# OECU_BASE2.net
KiCad netlist of a schematic drawn in Altium Designer
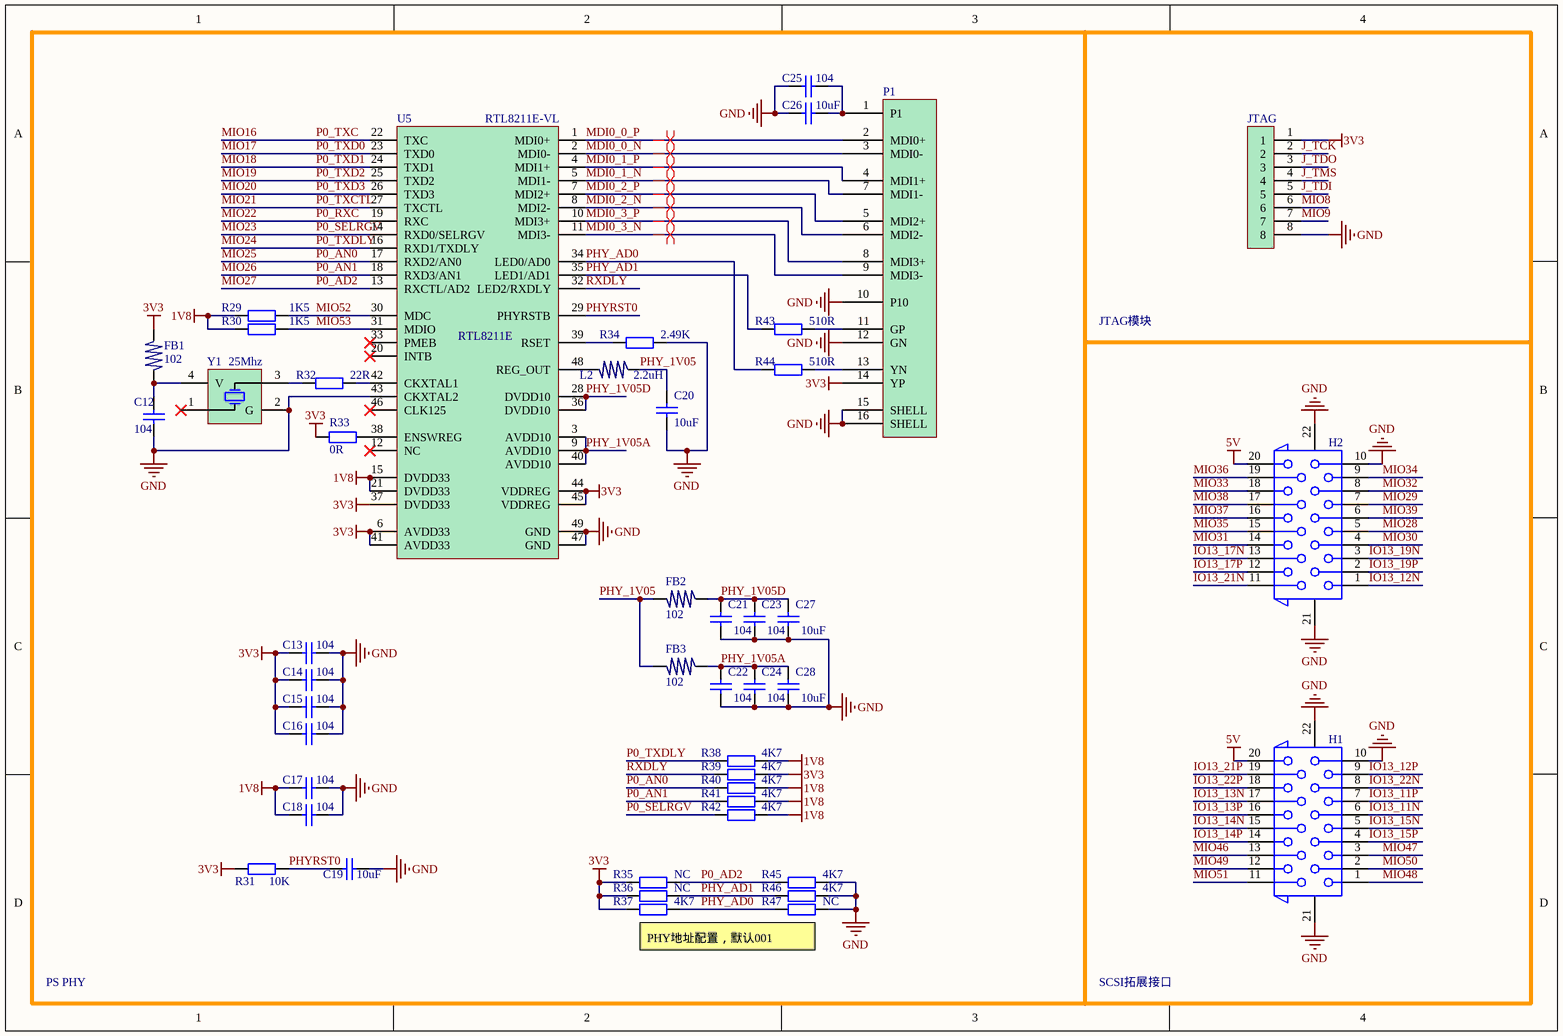
[diagram p0: OECU_BASE2.SchDoc]

(export (version "E")
  (design (tool "Eeschema 10.0.6"))
  (components
    (comp (ref "C12")
      (value "104")
      (footprint "0402")
      (description "贴片电容 0402")
      (libsource (lib "MT_Device") (part "CAP_0402"))
    )
    (comp (ref "C13")
      (value "104")
      (footprint "0402")
      (description "贴片电容 0402")
      (libsource (lib "MT_Device") (part "CAP_0402"))
    )
    (comp (ref "C14")
      (value "104")
      (footprint "0402")
      (description "贴片电容 0402")
      (libsource (lib "MT_Device") (part "CAP_0402"))
    )
    (comp (ref "C15")
      (value "104")
      (footprint "0402")
      (description "贴片电容 0402")
      (libsource (lib "MT_Device") (part "CAP_0402"))
    )
    (comp (ref "C16")
      (value "104")
      (footprint "0402")
      (description "贴片电容 0402")
      (libsource (lib "MT_Device") (part "CAP_0402"))
    )
    (comp (ref "C17")
      (value "104")
      (footprint "0402")
      (description "贴片电容 0402")
      (libsource (lib "MT_Device") (part "CAP_0402"))
    )
    (comp (ref "C18")
      (value "104")
      (footprint "0402")
      (description "贴片电容 0402")
      (libsource (lib "MT_Device") (part "CAP_0402"))
    )
    (comp (ref "C19")
      (value "10uF")
      (footprint "0402")
      (description "贴片电容 0402")
      (libsource (lib "MT_Device") (part "CAP_0402"))
    )
    (comp (ref "C20")
      (value "10uF")
      (footprint "0402")
      (description "贴片电容 0402")
      (libsource (lib "MT_Device") (part "CAP_0402"))
    )
    (comp (ref "C21")
      (value "104")
      (footprint "0402")
      (description "贴片电容 0402")
      (libsource (lib "MT_Device") (part "CAP_0402"))
    )
    (comp (ref "C22")
      (value "104")
      (footprint "0402")
      (description "贴片电容 0402")
      (libsource (lib "MT_Device") (part "CAP_0402"))
    )
    (comp (ref "C23")
      (value "104")
      (footprint "0402")
      (description "贴片电容 0402")
      (libsource (lib "MT_Device") (part "CAP_0402"))
    )
    (comp (ref "C24")
      (value "104")
      (footprint "0402")
      (description "贴片电容 0402")
      (libsource (lib "MT_Device") (part "CAP_0402"))
    )
    (comp (ref "C25")
      (value "104")
      (footprint "0402")
      (description "贴片电容 0402")
      (libsource (lib "MT_Device") (part "CAP_0402"))
    )
    (comp (ref "C26")
      (value "10uF")
      (footprint "0402")
      (description "贴片电容 0402")
      (libsource (lib "MT_Device") (part "CAP_0402"))
    )
    (comp (ref "C27")
      (value "10uF")
      (footprint "0402")
      (description "贴片电容 0402")
      (libsource (lib "MT_Device") (part "CAP_0402"))
    )
    (comp (ref "C28")
      (value "10uF")
      (footprint "0402")
      (description "贴片电容 0402")
      (libsource (lib "MT_Device") (part "CAP_0402"))
    )
    (comp (ref "FB1")
      (value "102")
      (footprint "0402")
      (description "磁珠 0402")
      (libsource (lib "MT_Device") (part "FB_0402"))
    )
    (comp (ref "FB2")
      (value "102")
      (footprint "0603")
      (description "磁珠 0603")
      (libsource (lib "MT_Device") (part "FB_0603"))
    )
    (comp (ref "FB3")
      (value "102")
      (footprint "0603")
      (description "磁珠 0603")
      (libsource (lib "MT_Device") (part "FB_0603"))
    )
    (comp (ref "H1")
      (value "SCSI20_1")
      (footprint "SCSI20_1")
      (libsource (lib "MT_Connector") (part "SCSI20_1"))
    )
    (comp (ref "H2")
      (value "SCSI20_1")
      (footprint "SCSI20_1")
      (libsource (lib "MT_Connector") (part "SCSI20_1"))
    )
    (comp (ref "JTAG")
      (value "SH1.25mm_8P")
      (footprint "SH1.25MM_8P")
      (libsource (lib "MT_Connector") (part "SH1.25mm_8P"))
    )
    (comp (ref "L2")
      (value "2.2uH")
      (footprint "0805")
      (description "电感 0805")
      (libsource (lib "MT_Device") (part "L_0805"))
    )
    (comp (ref "P1")
      (value "RJ45")
      (footprint "HR911130A")
      (libsource (lib "MT_Connector") (part "RJ45_HR911130A"))
    )
    (comp (ref "R29")
      (value "1K5")
      (footprint "R_0402")
      (description "电阻 0402")
      (libsource (lib "") (part "RES_0402_1"))
    )
    (comp (ref "R30")
      (value "1K5")
      (footprint "R_0402")
      (description "电阻 0402")
      (libsource (lib "") (part "RES_0402_1"))
    )
    (comp (ref "R31")
      (value "10K")
      (footprint "R_0402")
      (description "电阻 0402")
      (libsource (lib "") (part "RES_0402_2"))
    )
    (comp (ref "R32")
      (value "22R")
      (footprint "R_0402")
      (description "电阻 0402")
      (libsource (lib "") (part "RES_0402_1"))
    )
    (comp (ref "R33")
      (value "0R")
      (footprint "R_0402")
      (description "电阻 0402")
      (libsource (lib "") (part "RES_0402_1"))
    )
    (comp (ref "R34")
      (value "2.49K")
      (footprint "R_0402")
      (description "电阻 0402")
      (libsource (lib "MT_Device") (part "RES_0402"))
    )
    (comp (ref "R35")
      (value "NC")
      (footprint "R_0402")
      (description "电阻 0402")
      (libsource (lib "MT_Device") (part "RES_0402"))
    )
    (comp (ref "R36")
      (value "NC")
      (footprint "R_0402")
      (description "电阻 0402")
      (libsource (lib "MT_Device") (part "RES_0402"))
    )
    (comp (ref "R37")
      (value "4K7")
      (footprint "R_0402")
      (description "电阻 0402")
      (libsource (lib "MT_Device") (part "RES_0402"))
    )
    (comp (ref "R38")
      (value "4K7")
      (footprint "R_0402")
      (description "电阻 0402")
      (libsource (lib "MT_Device") (part "RES_0402"))
    )
    (comp (ref "R39")
      (value "4K7")
      (footprint "R_0402")
      (description "电阻 0402")
      (libsource (lib "MT_Device") (part "RES_0402"))
    )
    (comp (ref "R40")
      (value "4K7")
      (footprint "R_0402")
      (description "电阻 0402")
      (libsource (lib "MT_Device") (part "RES_0402"))
    )
    (comp (ref "R41")
      (value "4K7")
      (footprint "R_0402")
      (description "电阻 0402")
      (libsource (lib "MT_Device") (part "RES_0402"))
    )
    (comp (ref "R42")
      (value "4K7")
      (footprint "R_0402")
      (description "电阻 0402")
      (libsource (lib "MT_Device") (part "RES_0402"))
    )
    (comp (ref "R43")
      (value "510R")
      (footprint "R_0402")
      (description "电阻 0402")
      (libsource (lib "MT_Device") (part "RES_0402"))
    )
    (comp (ref "R44")
      (value "510R")
      (footprint "R_0402")
      (description "电阻 0402")
      (libsource (lib "MT_Device") (part "RES_0402"))
    )
    (comp (ref "R45")
      (value "4K7")
      (footprint "R_0402")
      (description "电阻 0402")
      (libsource (lib "MT_Device") (part "RES_0402"))
    )
    (comp (ref "R46")
      (value "4K7")
      (footprint "R_0402")
      (description "电阻 0402")
      (libsource (lib "MT_Device") (part "RES_0402"))
    )
    (comp (ref "R47")
      (value "NC")
      (footprint "R_0402")
      (description "电阻 0402")
      (libsource (lib "MT_Device") (part "RES_0402"))
    )
    (comp (ref "U5")
      (value "RTL8211E-VL")
      (footprint "QFN48")
      (description "QFN48")
      (libsource (lib "MT_Chip") (part "RTL8211E"))
    )
    (comp (ref "Y1")
      (value "25Mhz")
      (footprint "XTAL_3225")
      (description "贴片有源晶振")
      (libsource (lib "MT_Device") (part "XTAL_3225"))
    )
  )
  (nets
    (net (code "1") (name "/IO13_11N") (class "Default")
      (node (ref "H1") (pin "6") (pinfunction "6_6") (pintype "passive"))
    )
    (net (code "2") (name "/IO13_11P") (class "Default")
      (node (ref "H1") (pin "7") (pinfunction "7_7") (pintype "passive"))
    )
    (net (code "3") (name "/IO13_12N") (class "Default")
      (node (ref "H2") (pin "1") (pinfunction "1_1") (pintype "passive"))
    )
    (net (code "4") (name "/IO13_12P") (class "Default")
      (node (ref "H1") (pin "9") (pinfunction "9_9") (pintype "passive"))
    )
    (net (code "5") (name "/IO13_13N") (class "Default")
      (node (ref "H1") (pin "17") (pinfunction "17_17") (pintype "passive"))
    )
    (net (code "6") (name "/IO13_13P") (class "Default")
      (node (ref "H1") (pin "16") (pinfunction "16_16") (pintype "passive"))
    )
    (net (code "7") (name "/IO13_14N") (class "Default")
      (node (ref "H1") (pin "15") (pinfunction "15_15") (pintype "passive"))
    )
    (net (code "8") (name "/IO13_14P") (class "Default")
      (node (ref "H1") (pin "14") (pinfunction "14_14") (pintype "passive"))
    )
    (net (code "9") (name "/IO13_15N") (class "Default")
      (node (ref "H1") (pin "5") (pinfunction "5_5") (pintype "passive"))
    )
    (net (code "10") (name "/IO13_15P") (class "Default")
      (node (ref "H1") (pin "4") (pinfunction "4_4") (pintype "passive"))
    )
    (net (code "11") (name "/IO13_17N") (class "Default")
      (node (ref "H2") (pin "13") (pinfunction "13_13") (pintype "passive"))
    )
    (net (code "12") (name "/IO13_17P") (class "Default")
      (node (ref "H2") (pin "12") (pinfunction "12_12") (pintype "passive"))
    )
    (net (code "13") (name "/IO13_19N") (class "Default")
      (node (ref "H2") (pin "3") (pinfunction "3_3") (pintype "passive"))
    )
    (net (code "14") (name "/IO13_19P") (class "Default")
      (node (ref "H2") (pin "2") (pinfunction "2_2") (pintype "passive"))
    )
    (net (code "15") (name "/IO13_21N") (class "Default")
      (node (ref "H2") (pin "11") (pinfunction "11_11") (pintype "passive"))
    )
    (net (code "16") (name "/IO13_21P") (class "Default")
      (node (ref "H1") (pin "19") (pinfunction "19_19") (pintype "passive"))
    )
    (net (code "17") (name "/IO13_22N") (class "Default")
      (node (ref "H1") (pin "8") (pinfunction "8_8") (pintype "passive"))
    )
    (net (code "18") (name "/IO13_22P") (class "Default")
      (node (ref "H1") (pin "18") (pinfunction "18_18") (pintype "passive"))
    )
    (net (code "19") (name "/J_TCK") (class "Default")
      (node (ref "JTAG") (pin "2") (pinfunction "2_2") (pintype "passive"))
    )
    (net (code "20") (name "/J_TDI") (class "Default")
      (node (ref "JTAG") (pin "5") (pinfunction "5_5") (pintype "passive"))
    )
    (net (code "21") (name "/J_TDO") (class "Default")
      (node (ref "JTAG") (pin "3") (pinfunction "3_3") (pintype "passive"))
    )
    (net (code "22") (name "/J_TMS") (class "Default")
      (node (ref "JTAG") (pin "4") (pinfunction "4_4") (pintype "passive"))
    )
    (net (code "23") (name "/MDI0_0_N") (class "Default")
      (node (ref "P1") (pin "3") (pinfunction "MDI0-_3") (pintype "passive"))
      (node (ref "U5") (pin "2") (pinfunction "MDI0-_2") (pintype "passive"))
    )
    (net (code "24") (name "/MDI0_0_P") (class "Default")
      (node (ref "P1") (pin "2") (pinfunction "MDI0+_2") (pintype "passive"))
      (node (ref "U5") (pin "1") (pinfunction "MDI0+_1") (pintype "passive"))
    )
    (net (code "25") (name "/MDI0_1_N") (class "Default")
      (node (ref "P1") (pin "7") (pinfunction "MDI1-_7") (pintype "passive"))
      (node (ref "U5") (pin "5") (pinfunction "MDI1-_5") (pintype "passive"))
    )
    (net (code "26") (name "/MDI0_1_P") (class "Default")
      (node (ref "P1") (pin "4") (pinfunction "MDI1+_4") (pintype "passive"))
      (node (ref "U5") (pin "4") (pinfunction "MDI1+_4") (pintype "passive"))
    )
    (net (code "27") (name "/MDI0_2_N") (class "Default")
      (node (ref "P1") (pin "6") (pinfunction "MDI2-_6") (pintype "passive"))
      (node (ref "U5") (pin "8") (pinfunction "MDI2-_8") (pintype "passive"))
    )
    (net (code "28") (name "/MDI0_2_P") (class "Default")
      (node (ref "P1") (pin "5") (pinfunction "MDI2+_5") (pintype "passive"))
      (node (ref "U5") (pin "7") (pinfunction "MDI2+_7") (pintype "passive"))
    )
    (net (code "29") (name "/MDI0_3_N") (class "Default")
      (node (ref "P1") (pin "9") (pinfunction "MDI3-_9") (pintype "passive"))
      (node (ref "U5") (pin "11") (pinfunction "MDI3-_11") (pintype "passive"))
    )
    (net (code "30") (name "/MDI0_3_P") (class "Default")
      (node (ref "P1") (pin "8") (pinfunction "MDI3+_8") (pintype "passive"))
      (node (ref "U5") (pin "10") (pinfunction "MDI3+_10") (pintype "passive"))
    )
    (net (code "31") (name "/MIO8") (class "Default")
      (node (ref "JTAG") (pin "6") (pinfunction "6_6") (pintype "passive"))
    )
    (net (code "32") (name "/MIO9") (class "Default")
      (node (ref "JTAG") (pin "7") (pinfunction "7_7") (pintype "passive"))
    )
    (net (code "33") (name "/MIO16") (class "Default")
      (node (ref "U5") (pin "22") (pinfunction "TXC_22") (pintype "passive"))
    )
    (net (code "34") (name "/MIO17") (class "Default")
      (node (ref "U5") (pin "23") (pinfunction "TXD0_23") (pintype "passive"))
    )
    (net (code "35") (name "/MIO18") (class "Default")
      (node (ref "U5") (pin "24") (pinfunction "TXD1_24") (pintype "passive"))
    )
    (net (code "36") (name "/MIO19") (class "Default")
      (node (ref "U5") (pin "25") (pinfunction "TXD2_25") (pintype "passive"))
    )
    (net (code "37") (name "/MIO20") (class "Default")
      (node (ref "U5") (pin "26") (pinfunction "TXD3_26") (pintype "passive"))
    )
    (net (code "38") (name "/MIO21") (class "Default")
      (node (ref "U5") (pin "27") (pinfunction "TXCTL_27") (pintype "passive"))
    )
    (net (code "39") (name "/MIO22") (class "Default")
      (node (ref "U5") (pin "19") (pinfunction "RXC_19") (pintype "passive"))
    )
    (net (code "40") (name "/MIO23") (class "Default")
      (node (ref "R42") (pin "1") (pinfunction "1_1") (pintype "passive"))
      (node (ref "U5") (pin "14") (pinfunction "RXD0/SELRGV_14") (pintype "passive"))
    )
    (net (code "41") (name "/MIO24") (class "Default")
      (node (ref "R38") (pin "1") (pinfunction "1_1") (pintype "passive"))
      (node (ref "U5") (pin "16") (pinfunction "RXD1/TXDLY_16") (pintype "passive"))
    )
    (net (code "42") (name "/MIO25") (class "Default")
      (node (ref "R40") (pin "1") (pinfunction "1_1") (pintype "passive"))
      (node (ref "U5") (pin "17") (pinfunction "RXD2/AN0_17") (pintype "passive"))
    )
    (net (code "43") (name "/MIO26") (class "Default")
      (node (ref "R41") (pin "1") (pinfunction "1_1") (pintype "passive"))
      (node (ref "U5") (pin "18") (pinfunction "RXD3/AN1_18") (pintype "passive"))
    )
    (net (code "44") (name "/MIO27") (class "Default")
      (node (ref "R35") (pin "2") (pinfunction "2_2") (pintype "passive"))
      (node (ref "R45") (pin "1") (pinfunction "1_1") (pintype "passive"))
      (node (ref "U5") (pin "13") (pinfunction "RXCTL/AD2_13") (pintype "passive"))
    )
    (net (code "45") (name "/MIO28") (class "Default")
      (node (ref "H2") (pin "5") (pinfunction "5_5") (pintype "passive"))
    )
    (net (code "46") (name "/MIO29") (class "Default")
      (node (ref "H2") (pin "7") (pinfunction "7_7") (pintype "passive"))
    )
    (net (code "47") (name "/MIO30") (class "Default")
      (node (ref "H2") (pin "4") (pinfunction "4_4") (pintype "passive"))
    )
    (net (code "48") (name "/MIO31") (class "Default")
      (node (ref "H2") (pin "14") (pinfunction "14_14") (pintype "passive"))
    )
    (net (code "49") (name "/MIO32") (class "Default")
      (node (ref "H2") (pin "8") (pinfunction "8_8") (pintype "passive"))
    )
    (net (code "50") (name "/MIO33") (class "Default")
      (node (ref "H2") (pin "18") (pinfunction "18_18") (pintype "passive"))
    )
    (net (code "51") (name "/MIO34") (class "Default")
      (node (ref "H2") (pin "9") (pinfunction "9_9") (pintype "passive"))
    )
    (net (code "52") (name "/MIO35") (class "Default")
      (node (ref "H2") (pin "15") (pinfunction "15_15") (pintype "passive"))
    )
    (net (code "53") (name "/MIO36") (class "Default")
      (node (ref "H2") (pin "19") (pinfunction "19_19") (pintype "passive"))
    )
    (net (code "54") (name "/MIO37") (class "Default")
      (node (ref "H2") (pin "16") (pinfunction "16_16") (pintype "passive"))
    )
    (net (code "55") (name "/MIO38") (class "Default")
      (node (ref "H2") (pin "17") (pinfunction "17_17") (pintype "passive"))
    )
    (net (code "56") (name "/MIO39") (class "Default")
      (node (ref "H2") (pin "6") (pinfunction "6_6") (pintype "passive"))
    )
    (net (code "57") (name "/MIO46") (class "Default")
      (node (ref "H1") (pin "13") (pinfunction "13_13") (pintype "passive"))
    )
    (net (code "58") (name "/MIO47") (class "Default")
      (node (ref "H1") (pin "3") (pinfunction "3_3") (pintype "passive"))
    )
    (net (code "59") (name "/MIO48") (class "Default")
      (node (ref "H1") (pin "1") (pinfunction "1_1") (pintype "passive"))
    )
    (net (code "60") (name "/MIO49") (class "Default")
      (node (ref "H1") (pin "12") (pinfunction "12_12") (pintype "passive"))
    )
    (net (code "61") (name "/MIO50") (class "Default")
      (node (ref "H1") (pin "2") (pinfunction "2_2") (pintype "passive"))
    )
    (net (code "62") (name "/MIO51") (class "Default")
      (node (ref "H1") (pin "11") (pinfunction "11_11") (pintype "passive"))
    )
    (net (code "63") (name "/MIO52") (class "Default")
      (node (ref "R29") (pin "1") (pinfunction "1_1") (pintype "passive"))
      (node (ref "U5") (pin "30") (pinfunction "MDC_30") (pintype "passive"))
    )
    (net (code "64") (name "/MIO53") (class "Default")
      (node (ref "R30") (pin "1") (pinfunction "1_1") (pintype "passive"))
      (node (ref "U5") (pin "31") (pinfunction "MDIO_31") (pintype "passive"))
    )
    (net (code "65") (name "/PHYRST0") (class "Default")
      (node (ref "C19") (pin "1") (pinfunction "1_1") (pintype "passive"))
      (node (ref "R31") (pin "2") (pinfunction "2_2") (pintype "passive"))
      (node (ref "U5") (pin "29") (pinfunction "PHYRSTB_29") (pintype "passive"))
    )
    (net (code "66") (name "/PHY_1V05") (class "Default")
      (node (ref "C20") (pin "2") (pinfunction "2_2") (pintype "passive"))
      (node (ref "FB2") (pin "1") (pintype "passive"))
      (node (ref "FB3") (pin "1") (pintype "passive"))
      (node (ref "L2") (pin "1") (pintype "passive"))
    )
    (net (code "67") (name "/PHY_1V05A") (class "Default")
      (node (ref "C22") (pin "2") (pinfunction "2_2") (pintype "passive"))
      (node (ref "C24") (pin "2") (pinfunction "2_2") (pintype "passive"))
      (node (ref "C28") (pin "2") (pinfunction "2_2") (pintype "passive"))
      (node (ref "FB3") (pin "2") (pintype "passive"))
      (node (ref "U5") (pin "3") (pinfunction "AVDD10_3") (pintype "passive"))
      (node (ref "U5") (pin "40") (pinfunction "AVDD10_40") (pintype "passive"))
      (node (ref "U5") (pin "9") (pinfunction "AVDD10_9") (pintype "passive"))
    )
    (net (code "68") (name "/PHY_1V05D") (class "Default")
      (node (ref "C21") (pin "2") (pinfunction "2_2") (pintype "passive"))
      (node (ref "C23") (pin "2") (pinfunction "2_2") (pintype "passive"))
      (node (ref "C27") (pin "2") (pinfunction "2_2") (pintype "passive"))
      (node (ref "FB2") (pin "2") (pintype "passive"))
      (node (ref "U5") (pin "28") (pinfunction "DVDD10_28") (pintype "passive"))
      (node (ref "U5") (pin "36") (pinfunction "DVDD10_36") (pintype "passive"))
    )
    (net (code "69") (name "/PHY_AD0") (class "Default")
      (node (ref "R37") (pin "2") (pinfunction "2_2") (pintype "passive"))
      (node (ref "R44") (pin "1") (pinfunction "1_1") (pintype "passive"))
      (node (ref "R47") (pin "1") (pinfunction "1_1") (pintype "passive"))
      (node (ref "U5") (pin "34") (pinfunction "LED0/AD0_34") (pintype "passive"))
    )
    (net (code "70") (name "/PHY_AD1") (class "Default")
      (node (ref "R36") (pin "2") (pinfunction "2_2") (pintype "passive"))
      (node (ref "R43") (pin "1") (pinfunction "1_1") (pintype "passive"))
      (node (ref "R46") (pin "1") (pinfunction "1_1") (pintype "passive"))
      (node (ref "U5") (pin "35") (pinfunction "LED1/AD1_35") (pintype "passive"))
    )
    (net (code "71") (name "/RXDLY") (class "Default")
      (node (ref "R39") (pin "1") (pinfunction "1_1") (pintype "passive"))
      (node (ref "U5") (pin "32") (pinfunction "LED2/RXDLY_32") (pintype "passive"))
    )
    (net (code "72") (name "1V8") (class "Default")
      (node (ref "C17") (pin "1") (pinfunction "1_1") (pintype "passive"))
      (node (ref "C18") (pin "1") (pinfunction "1_1") (pintype "passive"))
      (node (ref "R29") (pin "2") (pinfunction "2_2") (pintype "passive"))
      (node (ref "R30") (pin "2") (pinfunction "2_2") (pintype "passive"))
      (node (ref "R38") (pin "2") (pinfunction "2_2") (pintype "passive"))
      (node (ref "R40") (pin "2") (pinfunction "2_2") (pintype "passive"))
      (node (ref "R41") (pin "2") (pinfunction "2_2") (pintype "passive"))
      (node (ref "R42") (pin "2") (pinfunction "2_2") (pintype "passive"))
      (node (ref "U5") (pin "15") (pinfunction "DVDD33_15") (pintype "passive"))
      (node (ref "U5") (pin "21") (pinfunction "DVDD33_21") (pintype "passive"))
    )
    (net (code "73") (name "3V3") (class "Default")
      (node (ref "C13") (pin "1") (pinfunction "1_1") (pintype "passive"))
      (node (ref "C14") (pin "1") (pinfunction "1_1") (pintype "passive"))
      (node (ref "C15") (pin "1") (pinfunction "1_1") (pintype "passive"))
      (node (ref "C16") (pin "1") (pinfunction "1_1") (pintype "passive"))
      (node (ref "FB1") (pin "2") (pintype "passive"))
      (node (ref "JTAG") (pin "1") (pinfunction "1_1") (pintype "passive"))
      (node (ref "P1") (pin "14") (pinfunction "YP_14") (pintype "passive"))
      (node (ref "R31") (pin "1") (pinfunction "1_1") (pintype "passive"))
      (node (ref "R33") (pin "2") (pinfunction "2_2") (pintype "passive"))
      (node (ref "R35") (pin "1") (pinfunction "1_1") (pintype "passive"))
      (node (ref "R36") (pin "1") (pinfunction "1_1") (pintype "passive"))
      (node (ref "R37") (pin "1") (pinfunction "1_1") (pintype "passive"))
      (node (ref "R39") (pin "2") (pinfunction "2_2") (pintype "passive"))
      (node (ref "U5") (pin "37") (pinfunction "DVDD33_37") (pintype "passive"))
      (node (ref "U5") (pin "41") (pinfunction "AVDD33_41") (pintype "passive"))
      (node (ref "U5") (pin "44") (pinfunction "VDDREG_44") (pintype "passive"))
      (node (ref "U5") (pin "45") (pinfunction "VDDREG_45") (pintype "passive"))
      (node (ref "U5") (pin "6") (pinfunction "AVDD33_6") (pintype "passive"))
    )
    (net (code "74") (name "5V") (class "Default")
      (node (ref "H1") (pin "20") (pinfunction "20_20") (pintype "passive"))
      (node (ref "H2") (pin "20") (pinfunction "20_20") (pintype "passive"))
    )
    (net (code "75") (name "GND") (class "Default")
      (node (ref "C12") (pin "1") (pinfunction "1_1") (pintype "passive"))
      (node (ref "C13") (pin "2") (pinfunction "2_2") (pintype "passive"))
      (node (ref "C14") (pin "2") (pinfunction "2_2") (pintype "passive"))
      (node (ref "C15") (pin "2") (pinfunction "2_2") (pintype "passive"))
      (node (ref "C16") (pin "2") (pinfunction "2_2") (pintype "passive"))
      (node (ref "C17") (pin "2") (pinfunction "2_2") (pintype "passive"))
      (node (ref "C18") (pin "2") (pinfunction "2_2") (pintype "passive"))
      (node (ref "C19") (pin "2") (pinfunction "2_2") (pintype "passive"))
      (node (ref "C20") (pin "1") (pinfunction "1_1") (pintype "passive"))
      (node (ref "C21") (pin "1") (pinfunction "1_1") (pintype "passive"))
      (node (ref "C22") (pin "1") (pinfunction "1_1") (pintype "passive"))
      (node (ref "C23") (pin "1") (pinfunction "1_1") (pintype "passive"))
      (node (ref "C24") (pin "1") (pinfunction "1_1") (pintype "passive"))
      (node (ref "C25") (pin "1") (pinfunction "1_1") (pintype "passive"))
      (node (ref "C26") (pin "1") (pinfunction "1_1") (pintype "passive"))
      (node (ref "C27") (pin "1") (pinfunction "1_1") (pintype "passive"))
      (node (ref "C28") (pin "1") (pinfunction "1_1") (pintype "passive"))
      (node (ref "H1") (pin "10") (pinfunction "10_10") (pintype "passive"))
      (node (ref "H1") (pin "21") (pinfunction "SHELL_21") (pintype "passive"))
      (node (ref "H1") (pin "22") (pinfunction "SHELL_22") (pintype "passive"))
      (node (ref "H2") (pin "10") (pinfunction "10_10") (pintype "passive"))
      (node (ref "H2") (pin "21") (pinfunction "SHELL_21") (pintype "passive"))
      (node (ref "H2") (pin "22") (pinfunction "SHELL_22") (pintype "passive"))
      (node (ref "JTAG") (pin "8") (pinfunction "8_8") (pintype "passive"))
      (node (ref "P1") (pin "10") (pinfunction "P10_10") (pintype "passive"))
      (node (ref "P1") (pin "12") (pinfunction "GN_12") (pintype "passive"))
      (node (ref "P1") (pin "15") (pinfunction "SHELL_15") (pintype "passive"))
      (node (ref "P1") (pin "16") (pinfunction "SHELL_16") (pintype "passive"))
      (node (ref "R34") (pin "2") (pinfunction "2_2") (pintype "passive"))
      (node (ref "R45") (pin "2") (pinfunction "2_2") (pintype "passive"))
      (node (ref "R46") (pin "2") (pinfunction "2_2") (pintype "passive"))
      (node (ref "R47") (pin "2") (pinfunction "2_2") (pintype "passive"))
      (node (ref "U5") (pin "43") (pinfunction "CKXTAL2_43") (pintype "passive"))
      (node (ref "U5") (pin "47") (pinfunction "GND_47") (pintype "passive"))
      (node (ref "U5") (pin "49") (pinfunction "GND_49") (pintype "passive"))
      (node (ref "Y1") (pin "2") (pinfunction "G_2") (pintype "passive"))
    )
    (net (code "76") (name "Net-(P1-GP)") (class "Default")
      (node (ref "P1") (pin "11") (pinfunction "GP_11") (pintype "passive"))
      (node (ref "R43") (pin "2") (pinfunction "2_2") (pintype "passive"))
    )
    (net (code "77") (name "Net-(P1-P1)") (class "Default")
      (node (ref "C25") (pin "2") (pinfunction "2_2") (pintype "passive"))
      (node (ref "C26") (pin "2") (pinfunction "2_2") (pintype "passive"))
      (node (ref "P1") (pin "1") (pinfunction "P1_1") (pintype "passive"))
    )
    (net (code "78") (name "Net-(P1-YN)") (class "Default")
      (node (ref "P1") (pin "13") (pinfunction "YN_13") (pintype "passive"))
      (node (ref "R44") (pin "2") (pinfunction "2_2") (pintype "passive"))
    )
    (net (code "79") (name "Net-(U5-CKXTAL1)") (class "Default")
      (node (ref "R32") (pin "1") (pinfunction "1_1") (pintype "passive"))
      (node (ref "U5") (pin "42") (pinfunction "CKXTAL1_42") (pintype "passive"))
    )
    (net (code "80") (name "Net-(U5-ENSWREG)") (class "Default")
      (node (ref "R33") (pin "1") (pinfunction "1_1") (pintype "passive"))
      (node (ref "U5") (pin "38") (pinfunction "ENSWREG_38") (pintype "passive"))
    )
    (net (code "81") (name "Net-(U5-REG_OUT)") (class "Default")
      (node (ref "L2") (pin "2") (pintype "passive"))
      (node (ref "U5") (pin "48") (pinfunction "REG_OUT_48") (pintype "passive"))
    )
    (net (code "82") (name "Net-(U5-RSET)") (class "Default")
      (node (ref "R34") (pin "1") (pinfunction "1_1") (pintype "passive"))
      (node (ref "U5") (pin "39") (pinfunction "RSET_39") (pintype "passive"))
    )
    (net (code "83") (name "Net-(Y1-OP)") (class "Default")
      (node (ref "R32") (pin "2") (pinfunction "2_2") (pintype "passive"))
      (node (ref "Y1") (pin "3") (pinfunction "OP_3") (pintype "passive"))
    )
    (net (code "84") (name "Net-(Y1-V)") (class "Default")
      (node (ref "C12") (pin "2") (pinfunction "2_2") (pintype "passive"))
      (node (ref "FB1") (pin "1") (pintype "passive"))
      (node (ref "Y1") (pin "4") (pinfunction "V_4") (pintype "passive"))
    )
    (net (code "85") (name "unconnected-(U5-CLK125-Pad46)") (class "Default")
      (node (ref "U5") (pin "46") (pinfunction "CLK125_46") (pintype "passive+no_connect"))
    )
    (net (code "86") (name "unconnected-(U5-INTB-Pad20)") (class "Default")
      (node (ref "U5") (pin "20") (pinfunction "INTB_20") (pintype "passive+no_connect"))
    )
    (net (code "87") (name "unconnected-(U5-NC-Pad12)") (class "Default")
      (node (ref "U5") (pin "12") (pinfunction "NC_12") (pintype "passive+no_connect"))
    )
    (net (code "88") (name "unconnected-(U5-PMEB-Pad33)") (class "Default")
      (node (ref "U5") (pin "33") (pinfunction "PMEB_33") (pintype "passive+no_connect"))
    )
    (net (code "89") (name "unconnected-(Y1-EC-Pad1)") (class "Default")
      (node (ref "Y1") (pin "1") (pinfunction "EC_1") (pintype "passive+no_connect"))
    )
  )
)
